# TX2.net
KiCad netlist of a schematic drawn in Altium Designer
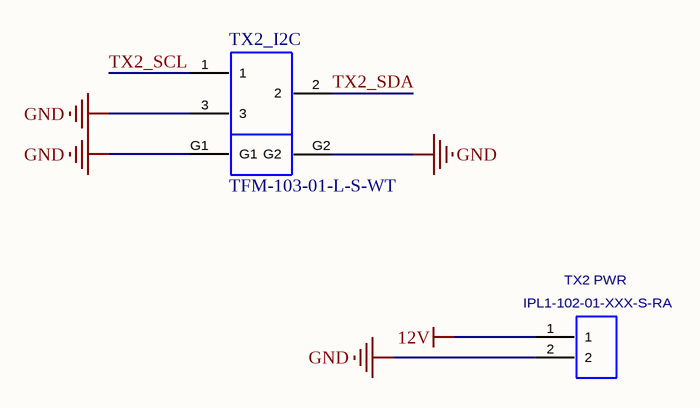
[diagram p0: TX2.SchDoc]

(export (version "E")
  (design (tool "Eeschema 10.0.6"))
  (components
    (comp (ref "TX2 PWR")
      (value "IPL1-102-01-XXX-S-RA")
      (footprint "IPL1-102-01-XXX-S-RA")
      (description "Terminal Assembly, Single Row, Right Angle, Thru-Hole, 2 Pins.")
      (fields (field (name "MANUFACTURER") "SAMTEC") (field (name "CREATED") "February 14, 2016 - Wendy Xin"))
      (libsource (lib "PDCB Lib Completed V4.2.0") (part "IPL1-102-01-XXX-S-RA"))
    )
    (comp (ref "TX2_I2C")
      (value "TFM-103-01-L-S-WT")
      (footprint "TFM-103-01-L-S-WT")
      (libsource (lib "PDCB Lib Completed V4.2.0") (part "TFM-103-01-L-S-WT"))
    )
  )
  (nets
    (net (code "1") (name "/TX2_SCL") (class "Default")
      (node (ref "TX2_I2C") (pin "1") (pinfunction "1_1") (pintype "passive"))
    )
    (net (code "2") (name "/TX2_SDA") (class "Default")
      (node (ref "TX2_I2C") (pin "2") (pinfunction "2_2") (pintype "passive"))
    )
    (net (code "3") (name "12V") (class "Default")
      (node (ref "TX2 PWR") (pin "1") (pinfunction "1_1") (pintype "passive"))
    )
    (net (code "4") (name "GND") (class "Default")
      (node (ref "TX2 PWR") (pin "2") (pinfunction "2_2") (pintype "passive"))
      (node (ref "TX2_I2C") (pin "3") (pinfunction "3_3") (pintype "passive"))
      (node (ref "TX2_I2C") (pin "G1") (pinfunction "G1_G1") (pintype "passive"))
      (node (ref "TX2_I2C") (pin "G2") (pinfunction "G2_G2") (pintype "passive"))
    )
  )
)
